# USB.net
KiCad netlist of a schematic drawn in Altium Designer
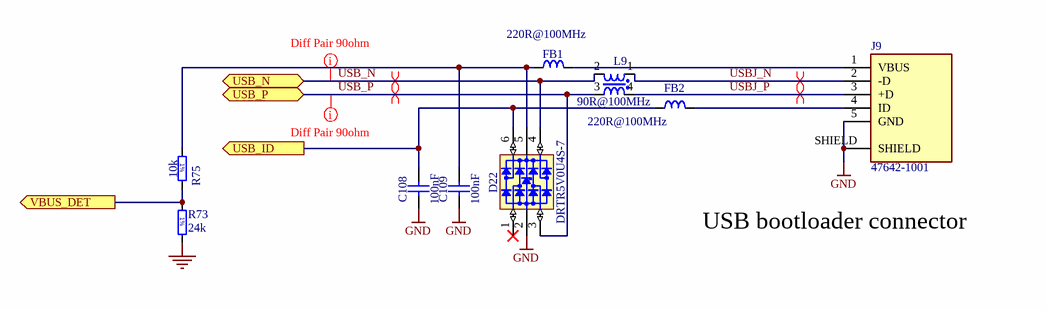
[diagram p0: USB.SchDoc]

(export (version "E")
  (design (tool "Eeschema 10.0.6"))
  (components
    (comp (ref "C108")
      (value "100nF")
      (footprint "CAPC1005X55N")
      (description "Non-polarised capacitor")
      (fields
        (field (name "PART NUMBER") "CC0402_100NF_16V_10%_X7R")
        (field (name "VOLTAGE") "16V")
        (field (name "AUTHOR") "CERN DEM JLC")
      )
      (libsource (lib "Capacitors") (part "Capacitor - non polarized"))
    )
    (comp (ref "C109")
      (value "100nF")
      (footprint "CAPC1005X55N")
      (description "Non-polarised capacitor")
      (fields
        (field (name "PART NUMBER") "CC0402_100NF_16V_10%_X7R")
        (field (name "VOLTAGE") "16V")
        (field (name "AUTHOR") "CERN DEM JLC")
      )
      (libsource (lib "Capacitors") (part "Capacitor - non polarized"))
    )
    (comp (ref "D22")
      (value "DRTR5V0U4S-7")
      (footprint "SOT65P210X110-6N")
      (description "Integrated Quad Ultra-Low Capacitance ESD Protection")
      (fields (field (name "MANUFACTURER") "DIODES") (field (name "AUTHOR") "GK"))
      (libsource (lib "Diodes") (part "D_TVS_DRTR5V0U4S-7"))
    )
    (comp (ref "FB1")
      (value "220R@100MHz")
      (footprint "INDC2012X105N")
      (description "Inductor")
      (fields
        (field (name "PART NUMBER") "IND0805_MURATA_BLM21PG221SN1D")
        (field (name "POWER") "2A")
        (field (name "AUTHOR") "CERN DEM JLC")
      )
      (libsource (lib "Inductors & Transformers") (part "Inductor"))
    )
    (comp (ref "FB2")
      (value "220R@100MHz")
      (footprint "INDC2012X105N")
      (description "Inductor")
      (fields
        (field (name "PART NUMBER") "IND0805_MURATA_BLM21PG221SN1D")
        (field (name "POWER") "2A")
        (field (name "AUTHOR") "CERN DEM JLC")
      )
      (libsource (lib "Inductors & Transformers") (part "Inductor"))
    )
    (comp (ref "J9")
      (value "47642-1001")
      (footprint "476421001")
      (description "Connector")
      (fields (field (name "MOUSER PART NUMBER") "538-47642-1001"))
      (libsource (lib "Integrated_Library_LOADER") (part "47642-1001"))
    )
    (comp (ref "L9")
      (value "90R@100MHz")
      (footprint "IND_MURATA_DLW21S")
      (description "Inductor Common Mode")
      (fields
        (field (name "PART NUMBER") "IND_MURATA_DLW21SN900SQ2L")
        (field (name "POWER") "330mA")
        (field (name "AUTHOR") "CERN DEM JLC")
      )
      (libsource (lib "Inductors & Transformers") (part "Inductor Common Mode 1Dot-2 4Dot-3"))
    )
    (comp (ref "R73")
      (value "24k")
      (footprint "RESC1608X55N")
      (description "Resistor - 1%")
      (fields
        (field (name "PART NUMBER") "R0603_24K_1%_0.1W_100PPM")
        (field (name "POWER") "0.1W")
        (field (name "AUTHOR") "CERN DEM JLC")
      )
      (libsource (lib "Resistors") (part "Resistor - 1%"))
    )
    (comp (ref "R75")
      (value "10k")
      (footprint "RESC1005X40N")
      (description "Resistor - 1%")
      (fields
        (field (name "PART NUMBER") "R0402_10K_1%_0.0625W_100PPM")
        (field (name "POWER") "0.0625W")
        (field (name "AUTHOR") "CERN DEM JLC")
      )
      (libsource (lib "Resistors") (part "Resistor - 1%"))
    )
  )
  (nets
    (net (code "1") (name "/USBJ_N") (class "Default")
      (node (ref "J9") (pin "2") (pinfunction "-D_2") (pintype "passive"))
      (node (ref "L9") (pin "1") (pinfunction "1_1") (pintype "passive"))
    )
    (net (code "2") (name "/USBJ_P") (class "Default")
      (node (ref "J9") (pin "3") (pinfunction "+D_3") (pintype "passive"))
      (node (ref "L9") (pin "4") (pinfunction "4_4") (pintype "passive"))
    )
    (net (code "3") (name "/USB_ID") (class "Default")
      (node (ref "C108") (pin "2") (pinfunction "2_2") (pintype "passive"))
      (node (ref "D22") (pin "6") (pinfunction "I/O4_6") (pintype "bidirectional"))
      (node (ref "FB2") (pin "1") (pinfunction "1_1") (pintype "passive"))
    )
    (net (code "4") (name "/USB_N") (class "Default")
      (node (ref "D22") (pin "4") (pinfunction "I/O3_4") (pintype "bidirectional"))
      (node (ref "L9") (pin "2") (pinfunction "2_2") (pintype "passive"))
    )
    (net (code "5") (name "/USB_P") (class "Default")
      (node (ref "D22") (pin "3") (pinfunction "I/O2_3") (pintype "bidirectional"))
      (node (ref "L9") (pin "3") (pinfunction "3_3") (pintype "passive"))
    )
    (net (code "6") (name "/VBUS_DET") (class "Default")
      (node (ref "R73") (pin "1") (pinfunction "1_1") (pintype "passive"))
      (node (ref "R75") (pin "2") (pinfunction "2_2") (pintype "passive"))
    )
    (net (code "7") (name "GND") (class "Default")
      (node (ref "C108") (pin "1") (pinfunction "1_1") (pintype "passive"))
      (node (ref "C109") (pin "1") (pinfunction "1_1") (pintype "passive"))
      (node (ref "D22") (pin "2") (pinfunction "GND_2") (pintype "power_in"))
      (node (ref "J9") (pin "5") (pinfunction "GND_5") (pintype "passive"))
      (node (ref "J9") (pin "SHIELD") (pinfunction "SHIELD_SHIELD") (pintype "passive"))
      (node (ref "R73") (pin "2") (pinfunction "2_2") (pintype "passive"))
    )
    (net (code "8") (name "Net-(D22-VBUS)") (class "Default")
      (node (ref "C109") (pin "2") (pinfunction "2_2") (pintype "passive"))
      (node (ref "D22") (pin "5") (pinfunction "VBUS_5") (pintype "power_in"))
      (node (ref "FB1") (pin "1") (pinfunction "1_1") (pintype "passive"))
      (node (ref "R75") (pin "1") (pinfunction "1_1") (pintype "passive"))
    )
    (net (code "9") (name "Net-(J9-ID)") (class "Default")
      (node (ref "FB2") (pin "2") (pinfunction "2_2") (pintype "passive"))
      (node (ref "J9") (pin "4") (pinfunction "ID_4") (pintype "passive"))
    )
    (net (code "10") (name "Net-(J9-VBUS)") (class "Default")
      (node (ref "FB1") (pin "2") (pinfunction "2_2") (pintype "passive"))
      (node (ref "J9") (pin "1") (pinfunction "VBUS_1") (pintype "passive"))
    )
    (net (code "11") (name "unconnected-(D22-I{slash}O1-Pad1)") (class "Default")
      (node (ref "D22") (pin "1") (pinfunction "I/O1_1") (pintype "bidirectional+no_connect"))
    )
  )
)
